# STeaMi-FP7-Port_extention.net
KiCad netlist of a schematic drawn in Altium Designer
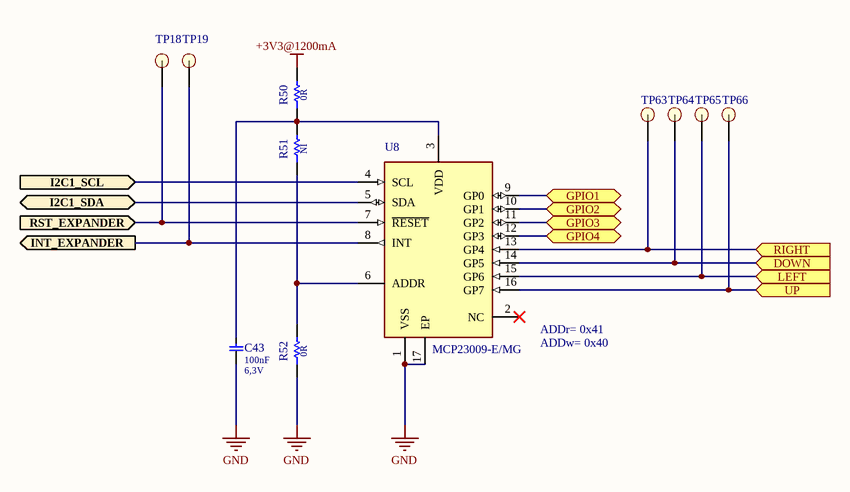
[diagram p0: STeaMi-FP7-Port_extention.SchDoc]

(export (version "E")
  (design (tool "Eeschema 10.0.6"))
  (components
    (comp (ref "C43")
      (value "~")
      (footprint "0402-CAP")
      (description "CAP CER 100nF 6,3V X5R 0402")
      (fields
        (field (name "MANUFACTURER") "Kyocera AVX")
        (field (name "MANUFACTURER PART NUMBER") "0402YD104KAT2A")
        (field (name "CAPACITANCE") "100nF")
        (field (name "VOLTAGE") "6,3V")
        (field (name "CREATED BY") "EAG")
        (field (name "CHECKED BY") "*")
      )
      (libsource (lib "ComponentDB") (part "CAP_SYMBOL"))
    )
    (comp (ref "R50")
      (value "~")
      (footprint "RESC1005X40N_0402")
      (description "RES CMS 0R5%-0,0625W-0402")
      (fields
        (field (name "MANUFACTURER") "Yageo")
        (field (name "MANUFACTURER PART NUMBER") "RC0402JR-100RL")
        (field (name "RESISTANCE") "0R")
        (field (name "CREATED BY") "EAG")
      )
      (libsource (lib "ComponentDB") (part "RES_SYMBOL"))
    )
    (comp (ref "R51")
      (value "~")
      (footprint "RESC1005X40N_0402")
      (description "NI")
      (fields
        (field (name "POWER") "0,1")
        (field (name "RESISTANCE") "NI")
        (field (name "PART NUMBER") "NI-1%-0,1W-0603")
        (field (name "CREATED BY") "MSA")
      )
      (libsource (lib "ComponentDB") (part "RES_SYMBOL"))
    )
    (comp (ref "R52")
      (value "~")
      (footprint "RESC1005X40N_0402")
      (description "RES CMS 0R5%-0,0625W-0402")
      (fields
        (field (name "MANUFACTURER") "Yageo")
        (field (name "MANUFACTURER PART NUMBER") "RC0402JR-100RL")
        (field (name "RESISTANCE") "0R")
        (field (name "CREATED BY") "EAG")
      )
      (libsource (lib "ComponentDB") (part "RES_SYMBOL"))
    )
    (comp (ref "TP18")
      (value "PAD")
      (footprint "Testpoint 1mm")
      (description "TESTPOINTPAD")
      (fields
        (field (name "MANUFACTURER") "Smartembed")
        (field (name "MANUFACTURER PART NUMBER") "TESTPOINT")
        (field (name "CREATED BY") "EAG")
      )
      (libsource (lib "ComponentDB") (part "TESTPOINT"))
    )
    (comp (ref "TP19")
      (value "PAD")
      (footprint "Testpoint 1mm")
      (description "TESTPOINTPAD")
      (fields
        (field (name "MANUFACTURER") "Smartembed")
        (field (name "MANUFACTURER PART NUMBER") "TESTPOINT")
        (field (name "CREATED BY") "EAG")
      )
      (libsource (lib "ComponentDB") (part "TESTPOINT"))
    )
    (comp (ref "TP63")
      (value "PAD")
      (footprint "Testpoint 1mm")
      (description "TESTPOINTPAD")
      (fields (field (name "MANUFACTURER") "SmartEmbed"))
      (libsource (lib "ComponentDB") (part "TESTPOINT"))
    )
    (comp (ref "TP64")
      (value "PAD")
      (footprint "Testpoint 1mm")
      (description "TESTPOINTPAD")
      (fields (field (name "MANUFACTURER") "SmartEmbed"))
      (libsource (lib "ComponentDB") (part "TESTPOINT"))
    )
    (comp (ref "TP65")
      (value "PAD")
      (footprint "Testpoint 1mm")
      (description "TESTPOINTPAD")
      (fields (field (name "MANUFACTURER") "SmartEmbed"))
      (libsource (lib "ComponentDB") (part "TESTPOINT"))
    )
    (comp (ref "TP66")
      (value "PAD")
      (footprint "Testpoint 1mm")
      (description "TESTPOINTPAD")
      (fields (field (name "MANUFACTURER") "SmartEmbed"))
      (libsource (lib "ComponentDB") (part "TESTPOINT"))
    )
    (comp (ref "U8")
      (value "~")
      (footprint "QFN50P300X300X100-17N-D")
      (description "Interface - Extensions d'E/S 8B I/O Expander I2C interface")
      (fields
        (field (name "MANUFACTURER") "Microchip")
        (field (name "MANUFACTURER PART NUMBER") "MCP23009-E/MG")
        (field (name "PART NUMBER") "MCP23009-E/MG")
        (field (name "CREATED BY") "EAG")
        (field (name "CHECKED BY") "*")
      )
      (libsource (lib "ComponentDB") (part "MCP23009-E/MG"))
    )
  )
  (nets
    (net (code "1") (name "+3V3@1200mA") (class "Default")
      (node (ref "R50") (pin "2") (pinfunction "2_2") (pintype "passive"))
    )
    (net (code "2") (name "/DOWN") (class "Default")
      (node (ref "TP64") (pin "1") (pinfunction "1_1") (pintype "passive"))
      (node (ref "U8") (pin "14") (pinfunction "GP5_14") (pintype "input"))
    )
    (net (code "3") (name "/GPIO1") (class "Default")
      (node (ref "U8") (pin "9") (pinfunction "GP0_9") (pintype "bidirectional"))
    )
    (net (code "4") (name "/GPIO2") (class "Default")
      (node (ref "U8") (pin "10") (pinfunction "GP1_10") (pintype "bidirectional"))
    )
    (net (code "5") (name "/GPIO3") (class "Default")
      (node (ref "U8") (pin "11") (pinfunction "GP2_11") (pintype "bidirectional"))
    )
    (net (code "6") (name "/GPIO4") (class "Default")
      (node (ref "U8") (pin "12") (pinfunction "GP3_12") (pintype "bidirectional"))
    )
    (net (code "7") (name "/I2C1_SCL") (class "Default")
      (node (ref "U8") (pin "4") (pinfunction "SCL_4") (pintype "input"))
    )
    (net (code "8") (name "/I2C1_SDA") (class "Default")
      (node (ref "U8") (pin "5") (pinfunction "SDA_5") (pintype "bidirectional"))
    )
    (net (code "9") (name "/INT_EXPANDER") (class "Default")
      (node (ref "TP19") (pin "1") (pinfunction "1_1") (pintype "passive"))
      (node (ref "U8") (pin "8") (pinfunction "INT_8") (pintype "output"))
    )
    (net (code "10") (name "/LEFT") (class "Default")
      (node (ref "TP65") (pin "1") (pinfunction "1_1") (pintype "passive"))
      (node (ref "U8") (pin "15") (pinfunction "GP6_15") (pintype "input"))
    )
    (net (code "11") (name "/RIGHT") (class "Default")
      (node (ref "TP63") (pin "1") (pinfunction "1_1") (pintype "passive"))
      (node (ref "U8") (pin "13") (pinfunction "GP4_13") (pintype "input"))
    )
    (net (code "12") (name "/RST_EXPANDER") (class "Default")
      (node (ref "TP18") (pin "1") (pinfunction "1_1") (pintype "passive"))
      (node (ref "U8") (pin "7") (pinfunction "~{RESET}_7") (pintype "input"))
    )
    (net (code "13") (name "/UP") (class "Default")
      (node (ref "TP66") (pin "1") (pinfunction "1_1") (pintype "passive"))
      (node (ref "U8") (pin "16") (pinfunction "GP7_16") (pintype "input"))
    )
    (net (code "14") (name "GND") (class "Default")
      (node (ref "C43") (pin "1") (pinfunction "1_1") (pintype "passive"))
      (node (ref "R52") (pin "1") (pinfunction "1_1") (pintype "passive"))
      (node (ref "U8") (pin "1") (pinfunction "VSS_1") (pintype "power_in"))
      (node (ref "U8") (pin "17") (pinfunction "EP_17") (pintype "passive"))
    )
    (net (code "15") (name "Net-(U8-ADDR)") (class "Default")
      (node (ref "R51") (pin "1") (pinfunction "1_1") (pintype "passive"))
      (node (ref "R52") (pin "2") (pinfunction "2_2") (pintype "passive"))
      (node (ref "U8") (pin "6") (pinfunction "ADDR_6") (pintype "passive"))
    )
    (net (code "16") (name "Net-(U8-VDD)") (class "Default")
      (node (ref "C43") (pin "2") (pinfunction "2_2") (pintype "passive"))
      (node (ref "R50") (pin "1") (pinfunction "1_1") (pintype "passive"))
      (node (ref "R51") (pin "2") (pinfunction "2_2") (pintype "passive"))
      (node (ref "U8") (pin "3") (pinfunction "VDD_3") (pintype "power_in"))
    )
    (net (code "17") (name "unconnected-(U8-NC-Pad2)") (class "Default")
      (node (ref "U8") (pin "2") (pinfunction "NC_2") (pintype "passive+no_connect"))
    )
  )
)
